# CH32V307_V2_0_0.net
KiCad netlist of a schematic drawn in EasyEDA Pro
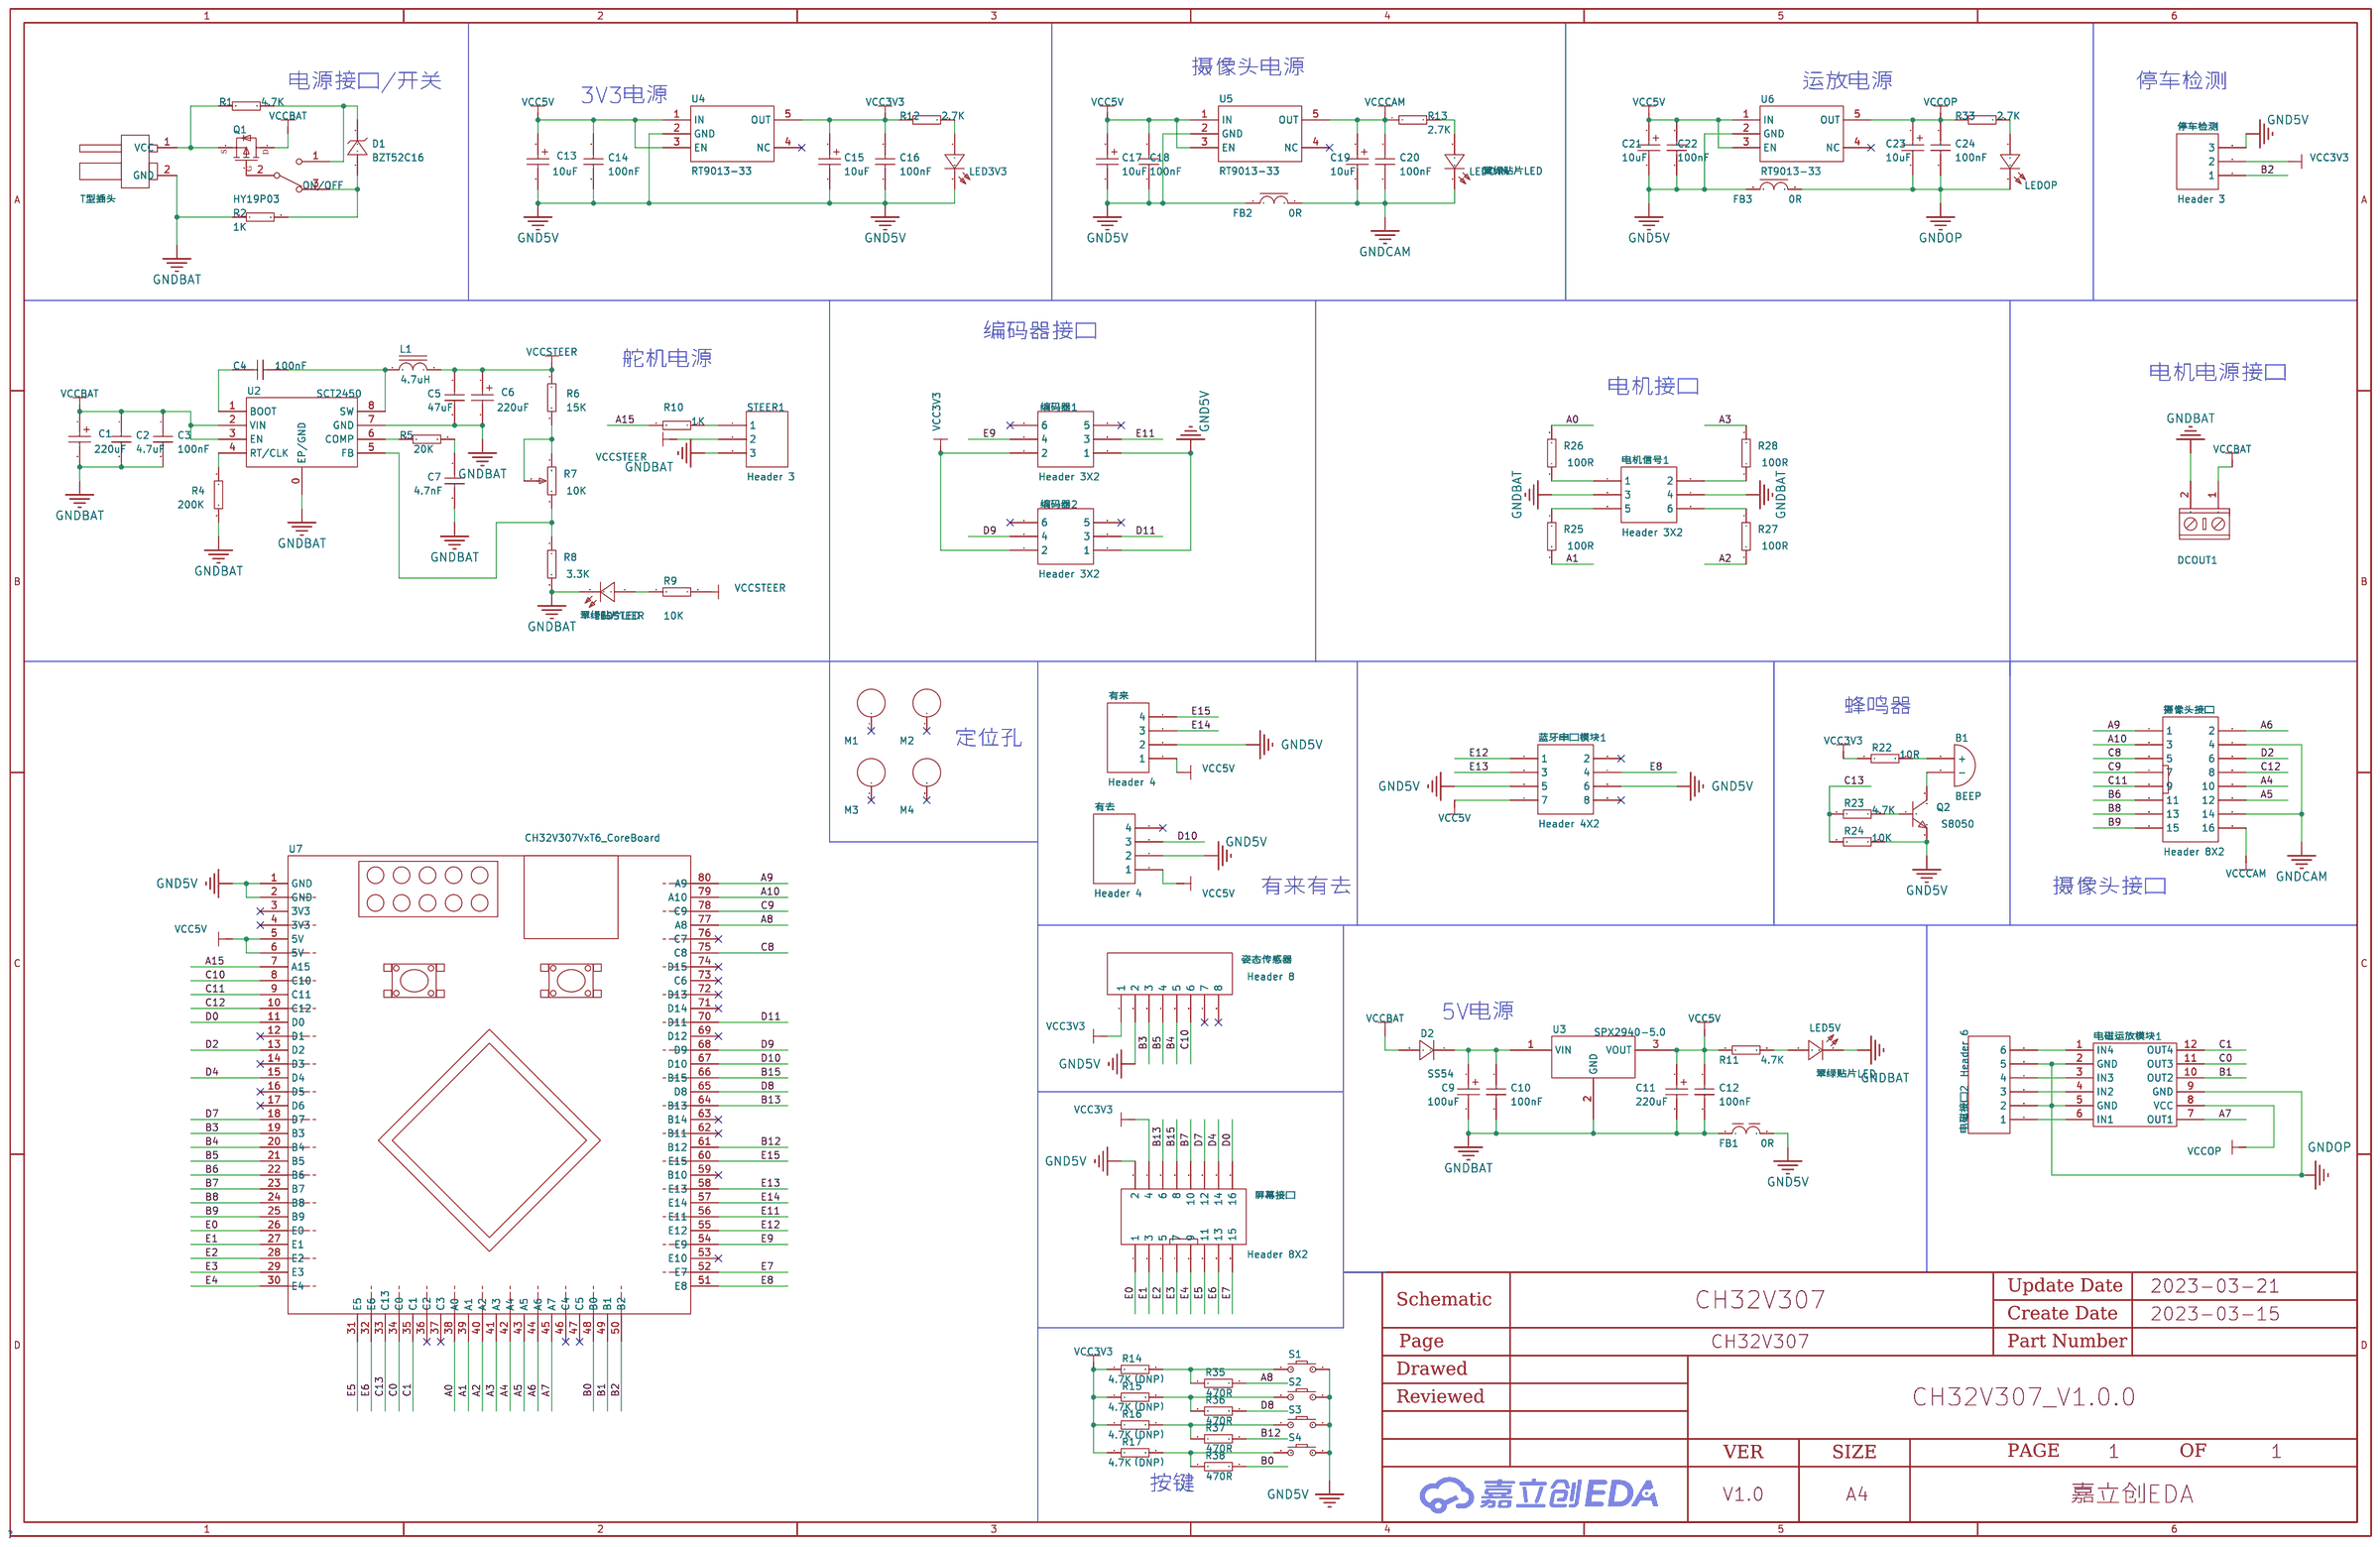
[diagram p0: schematic sheet]

(export (version "E")
  (design (tool "Eeschema 10.0.6"))
  (components
    (comp (ref "B1")
      (value "BEEP")
      (footprint "easyedapro:BEEP 9x5.5mm")
      (libsource (lib "easyedapro") (part "BEEP"))
    )
    (comp (ref "C1")
      (value "220uF")
      (footprint "easyedapro:CAPS6.3")
      (fields (field (name "Voltage") "25V") (field (name "Publisher") "Altium Limited"))
      (libsource (lib "easyedapro") (part "Cap-Solid_1"))
    )
    (comp (ref "C2")
      (value "4.7nF")
      (footprint "easyedapro:CAPC1608[0603]S-N")
      (fields (field (name "Tolerance") "±10%") (field (name "Voltage") "50V"))
      (libsource (lib "easyedapro") (part "Cap-Chip_3"))
    )
    (comp (ref "C3")
      (value "100nF")
      (footprint "easyedapro:CAPC1608[0603]S-N")
      (fields (field (name "Tolerance") "±10%") (field (name "Voltage") "50V"))
      (libsource (lib "easyedapro") (part "Cap-Chip"))
    )
    (comp (ref "C4")
      (value "100nF")
      (footprint "easyedapro:CAPC1608[0603]S-N")
      (libsource (lib "easyedapro") (part "Cap-Chip"))
    )
    (comp (ref "C5")
      (value "47uF")
      (footprint "easyedapro:CAPC3216[1206]S")
      (fields (field (name "Tolerance") "±10%") (field (name "Voltage") "16V"))
      (libsource (lib "easyedapro") (part "Cap-Chip_2"))
    )
    (comp (ref "C6")
      (value "220uF")
      (footprint "easyedapro:CAPS6.3")
      (fields (field (name "Voltage") "25V") (field (name "Publisher") "Altium Limited"))
      (libsource (lib "easyedapro") (part "Cap-Solid_1"))
    )
    (comp (ref "C7")
      (value "4.7nF")
      (footprint "easyedapro:CAPC1608[0603]S-N")
      (fields (field (name "Tolerance") "±10%") (field (name "Voltage") "50V"))
      (libsource (lib "easyedapro") (part "Cap-Chip_3"))
    )
    (comp (ref "C9")
      (value "100uF")
      (footprint "easyedapro:CAPS6.3")
      (fields (field (name "Voltage") "25V") (field (name "Publisher") "Altium Limited"))
      (libsource (lib "easyedapro") (part "Cap-Solid"))
    )
    (comp (ref "C10")
      (value "100nF")
      (footprint "easyedapro:CAPC1608[0603]S-N")
      (fields (field (name "Tolerance") "±10%") (field (name "Voltage") "50V"))
      (libsource (lib "easyedapro") (part "Cap-Chip"))
    )
    (comp (ref "C11")
      (value "220uF")
      (footprint "easyedapro:CAPS6.3")
      (fields (field (name "Voltage") "25V") (field (name "Publisher") "Altium Limited"))
      (libsource (lib "easyedapro") (part "Cap-Solid_1"))
    )
    (comp (ref "C12")
      (value "100nF")
      (footprint "easyedapro:CAPC1608[0603]S-N")
      (fields (field (name "Tolerance") "±10%") (field (name "Voltage") "50V"))
      (libsource (lib "easyedapro") (part "Cap-Chip"))
    )
    (comp (ref "C13")
      (value "10uF")
      (footprint "easyedapro:CAPT3216")
      (fields (field (name "Voltage") "16V") (field (name "Publisher") "Altium Limited"))
      (libsource (lib "easyedapro") (part "Cap-Tan"))
    )
    (comp (ref "C14")
      (value "100nF")
      (footprint "easyedapro:CAPC1608[0603]S-N")
      (fields (field (name "Tolerance") "±10%") (field (name "Voltage") "50V"))
      (libsource (lib "easyedapro") (part "Cap-Chip"))
    )
    (comp (ref "C15")
      (value "10uF")
      (footprint "easyedapro:CAPT3216")
      (fields (field (name "Voltage") "16V") (field (name "Publisher") "Altium Limited"))
      (libsource (lib "easyedapro") (part "Cap-Tan"))
    )
    (comp (ref "C16")
      (value "100nF")
      (footprint "easyedapro:CAPC1608[0603]S-N")
      (fields (field (name "Tolerance") "±10%") (field (name "Voltage") "50V"))
      (libsource (lib "easyedapro") (part "Cap-Chip"))
    )
    (comp (ref "C17")
      (value "10uF")
      (footprint "easyedapro:CAPT3216")
      (fields (field (name "Voltage") "16V") (field (name "Publisher") "Altium Limited"))
      (libsource (lib "easyedapro") (part "Cap-Tan"))
    )
    (comp (ref "C18")
      (value "100nF")
      (footprint "easyedapro:CAPC1608[0603]S-N")
      (fields (field (name "Tolerance") "±10%") (field (name "Voltage") "50V"))
      (libsource (lib "easyedapro") (part "Cap-Chip"))
    )
    (comp (ref "C19")
      (value "10uF")
      (footprint "easyedapro:CAPT3216")
      (fields (field (name "Voltage") "16V") (field (name "Publisher") "Altium Limited"))
      (libsource (lib "easyedapro") (part "Cap-Tan"))
    )
    (comp (ref "C20")
      (value "100nF")
      (footprint "easyedapro:CAPC1608[0603]S-N")
      (fields (field (name "Tolerance") "±10%") (field (name "Voltage") "50V"))
      (libsource (lib "easyedapro") (part "Cap-Chip"))
    )
    (comp (ref "C21")
      (value "10uF")
      (footprint "easyedapro:CAPT3216")
      (fields (field (name "Voltage") "16V") (field (name "Publisher") "Altium Limited"))
      (libsource (lib "easyedapro") (part "Cap-Tan"))
    )
    (comp (ref "C22")
      (value "100nF")
      (footprint "easyedapro:CAPC1608[0603]S-N")
      (fields (field (name "Tolerance") "±10%") (field (name "Voltage") "50V"))
      (libsource (lib "easyedapro") (part "Cap-Chip"))
    )
    (comp (ref "C23")
      (value "10uF")
      (footprint "easyedapro:CAPT3216")
      (fields (field (name "Voltage") "16V") (field (name "Publisher") "Altium Limited"))
      (libsource (lib "easyedapro") (part "Cap-Tan"))
    )
    (comp (ref "C24")
      (value "100nF")
      (footprint "easyedapro:CAPC1608[0603]S-N")
      (fields (field (name "Tolerance") "±10%") (field (name "Voltage") "50V"))
      (libsource (lib "easyedapro") (part "Cap-Chip"))
    )
    (comp (ref "D1")
      (value "BZT52C16")
      (footprint "easyedapro:SOD-123-L")
      (fields (field (name "Publisher") "Altium Limited"))
      (libsource (lib "easyedapro") (part "Diode TVS Uni-Dir"))
    )
    (comp (ref "D2")
      (value "SS54")
      (footprint "easyedapro:SMA[DO-214AC]")
      (libsource (lib "easyedapro") (part "Diode"))
    )
    (comp (ref "DCOUT1")
      (value "KF/WJ/DG 30x connecter")
      (footprint "easyedapro:KF/WJ/DG 301-2p-5.0mm")
      (libsource (lib "easyedapro") (part "KF/WJ/DG 30x"))
    )
    (comp (ref "FB1")
      (value "0R")
      (footprint "easyedapro:INDC2012[0805]S")
      (libsource (lib "easyedapro") (part "Ind Chip 2"))
    )
    (comp (ref "FB2")
      (value "0R")
      (footprint "easyedapro:INDC2012[0805]S")
      (libsource (lib "easyedapro") (part "Ind-Chip"))
    )
    (comp (ref "FB3")
      (value "0R")
      (footprint "easyedapro:INDC2012[0805]S")
      (libsource (lib "easyedapro") (part "Ind-Chip"))
    )
    (comp (ref "L1")
      (value "4.7uH")
      (footprint "easyedapro:0630 TPC 7*7*3")
      (libsource (lib "easyedapro") (part "Ind-Power"))
    )
    (comp (ref "LED3V3")
      (value "翠绿贴片LED")
      (footprint "easyedapro:LEDC1608(0603)")
      (fields (field (name "Publisher") "Altium Limited"))
      (libsource (lib "easyedapro") (part "LED Chip Green"))
    )
    (comp (ref "LED5V")
      (value "翠绿贴片LED")
      (footprint "easyedapro:LEDC1608(0603)")
      (libsource (lib "easyedapro") (part "LED Chip Green"))
    )
    (comp (ref "LEDCAM")
      (value "翠绿贴片LED")
      (footprint "easyedapro:LEDC1608(0603)")
      (fields (field (name "Publisher") "Altium Limited"))
      (libsource (lib "easyedapro") (part "LED Chip Green"))
    )
    (comp (ref "LEDOP")
      (value "翠绿贴片LED")
      (footprint "easyedapro:LEDC1608(0603)")
      (fields (field (name "Publisher") "Altium Limited"))
      (libsource (lib "easyedapro") (part "LED Chip Green"))
    )
    (comp (ref "LEDSTEER")
      (value "翠绿贴片LED")
      (footprint "easyedapro:LEDC1608(0603)")
      (fields (field (name "Publisher") "Altium Limited"))
      (libsource (lib "easyedapro") (part "LED Chip Green"))
    )
    (comp (ref "M1")
      (value "MountHole")
      (footprint "easyedapro:M3-MountHole-Plated")
      (libsource (lib "easyedapro") (part "MountHole"))
    )
    (comp (ref "M2")
      (value "MountHole")
      (footprint "easyedapro:M3-MountHole-Plated")
      (libsource (lib "easyedapro") (part "MountHole"))
    )
    (comp (ref "M3")
      (value "MountHole")
      (footprint "easyedapro:M3-MountHole-Plated")
      (libsource (lib "easyedapro") (part "MountHole"))
    )
    (comp (ref "M4")
      (value "MountHole")
      (footprint "easyedapro:M3-MountHole-Plated")
      (libsource (lib "easyedapro") (part "MountHole"))
    )
    (comp (ref "ON/OFF")
      (value "SW-SPDT")
      (footprint "easyedapro:SS12D10")
      (fields (field (name "Publisher") "Altium Limited"))
      (libsource (lib "easyedapro") (part "SW-SPDT"))
    )
    (comp (ref "Q1")
      (value "HY19P03")
      (footprint "easyedapro:TO-252AA")
      (libsource (lib "easyedapro") (part "HY19P03"))
    )
    (comp (ref "Q2")
      (value "S8050")
      (footprint "easyedapro:SOT-23")
      (libsource (lib "easyedapro") (part "NPN S8050"))
    )
    (comp (ref "R1")
      (value "4.7K")
      (footprint "easyedapro:RESC1608[0603]S-N")
      (libsource (lib "easyedapro") (part "Res-Chip_2"))
    )
    (comp (ref "R2")
      (value "1K")
      (footprint "easyedapro:RESC1608[0603]S-N")
      (libsource (lib "easyedapro") (part "Res-Chip_1"))
    )
    (comp (ref "R4")
      (value "200K")
      (footprint "easyedapro:RESC1608[0603]S-N")
      (fields (field (name "Tolerance") "±1%"))
      (libsource (lib "easyedapro") (part "Res-Chip_4"))
    )
    (comp (ref "R5")
      (value "20K")
      (footprint "easyedapro:RESC1608[0603]S-N")
      (libsource (lib "easyedapro") (part "Res-Chip_5"))
    )
    (comp (ref "R6")
      (value "15K")
      (footprint "easyedapro:RESC1608[0603]S-N")
      (fields (field (name "Tolerance") "±1%"))
      (libsource (lib "easyedapro") (part "Res-Chip_6"))
    )
    (comp (ref "R7")
      (value "10K")
      (footprint "easyedapro:RESPOT3296")
      (libsource (lib "easyedapro") (part "Res-Adj-3p"))
    )
    (comp (ref "R8")
      (value "3.3K")
      (footprint "easyedapro:RESC1608[0603]S-N")
      (fields (field (name "Tolerance") "±1%"))
      (libsource (lib "easyedapro") (part "Res-Chip_7"))
    )
    (comp (ref "R9")
      (value "10K")
      (footprint "easyedapro:RESC1608[0603]S-N")
      (libsource (lib "easyedapro") (part "Res-Chip"))
    )
    (comp (ref "R10")
      (value "1K")
      (footprint "easyedapro:RESC1608[0603]S-N")
      (fields (field (name "Tolerance") "±1%"))
      (libsource (lib "easyedapro") (part "Res-Chip_1"))
    )
    (comp (ref "R11")
      (value "4.7K")
      (footprint "easyedapro:RESC1608[0603]S-N")
      (libsource (lib "easyedapro") (part "Res-Chip_2"))
    )
    (comp (ref "R12")
      (value "2.7K")
      (footprint "easyedapro:RESC1608[0603]S-N")
      (libsource (lib "easyedapro") (part "Res-Chip_3"))
    )
    (comp (ref "R13")
      (value "2.7K")
      (footprint "easyedapro:RESC1608[0603]S-N")
      (libsource (lib "easyedapro") (part "Res-Chip_3"))
    )
    (comp (ref "R14")
      (value "4.7K(DNP)")
      (footprint "easyedapro:RESC1608[0603]S-N")
      (libsource (lib "easyedapro") (part "Res-Chip_9"))
    )
    (comp (ref "R15")
      (value "4.7K(DNP)")
      (footprint "easyedapro:RESC1608[0603]S-N")
      (libsource (lib "easyedapro") (part "Res-Chip_9"))
    )
    (comp (ref "R16")
      (value "4.7K(DNP)")
      (footprint "easyedapro:RESC1608[0603]S-N")
      (libsource (lib "easyedapro") (part "Res-Chip_9"))
    )
    (comp (ref "R17")
      (value "4.7K(DNP)")
      (footprint "easyedapro:RESC1608[0603]S-N")
      (libsource (lib "easyedapro") (part "Res-Chip_9"))
    )
    (comp (ref "R22")
      (value "10R")
      (footprint "easyedapro:RESC1608[0603]S-N")
      (libsource (lib "easyedapro") (part "Res-Chip_10"))
    )
    (comp (ref "R23")
      (value "4.7K")
      (footprint "easyedapro:RESC1608[0603]S-N")
      (libsource (lib "easyedapro") (part "Res-Chip_2"))
    )
    (comp (ref "R24")
      (value "10K")
      (footprint "easyedapro:RESC1608[0603]S-N")
      (libsource (lib "easyedapro") (part "Res-Chip"))
    )
    (comp (ref "R25")
      (value "100R")
      (footprint "easyedapro:RESC1608[0603]S-N")
      (libsource (lib "easyedapro") (part "Res-Chip_8"))
    )
    (comp (ref "R26")
      (value "100R")
      (footprint "easyedapro:RESC1608[0603]S-N")
      (libsource (lib "easyedapro") (part "Res-Chip_8"))
    )
    (comp (ref "R27")
      (value "100R")
      (footprint "easyedapro:RESC1608[0603]S-N")
      (fields (field (name "Tolerance") "±1%"))
      (libsource (lib "easyedapro") (part "Res-Chip_8"))
    )
    (comp (ref "R28")
      (value "100R")
      (footprint "easyedapro:RESC1608[0603]S-N")
      (libsource (lib "easyedapro") (part "Res-Chip_8"))
    )
    (comp (ref "R33")
      (value "2.7K")
      (footprint "easyedapro:RESC1608[0603]S-N")
      (libsource (lib "easyedapro") (part "Res-Chip_3"))
    )
    (comp (ref "R35")
      (value "470R")
      (footprint "easyedapro:RESC1608[0603]S-N")
      (libsource (lib "easyedapro") (part "Res-Chip_11"))
    )
    (comp (ref "R36")
      (value "470R")
      (footprint "easyedapro:RESC1608[0603]S-N")
      (libsource (lib "easyedapro") (part "Res-Chip_11"))
    )
    (comp (ref "R37")
      (value "470R")
      (footprint "easyedapro:RESC1608[0603]S-N")
      (libsource (lib "easyedapro") (part "Res-Chip_11"))
    )
    (comp (ref "R38")
      (value "470R")
      (footprint "easyedapro:RESC1608[0603]S-N")
      (libsource (lib "easyedapro") (part "Res-Chip_11"))
    )
    (comp (ref "S1")
      (value "Button")
      (footprint "easyedapro:PTS810-3*4-CurvePin")
      (libsource (lib "easyedapro") (part "KEY"))
    )
    (comp (ref "S2")
      (value "Button")
      (footprint "easyedapro:PTS810-3*4-CurvePin")
      (libsource (lib "easyedapro") (part "KEY"))
    )
    (comp (ref "S3")
      (value "Button")
      (footprint "easyedapro:PTS810-3*4-CurvePin")
      (libsource (lib "easyedapro") (part "KEY"))
    )
    (comp (ref "S4")
      (value "Button")
      (footprint "easyedapro:PTS810-3*4-CurvePin")
      (libsource (lib "easyedapro") (part "KEY"))
    )
    (comp (ref "STEER1")
      (value "Header 3")
      (footprint "easyedapro:HDR1X3")
      (fields (field (name "Publisher") "Altium Limited"))
      (libsource (lib "easyedapro") (part "Header 3"))
    )
    (comp (ref "U1")
      (value "T型插头")
      (footprint "easyedapro:Wired T-Header ThroughHole")
      (libsource (lib "easyedapro") (part "T_Header"))
    )
    (comp (ref "U2")
      (value "SCT2450")
      (footprint "easyedapro:SOP-8E")
      (libsource (lib "easyedapro") (part "SCT2450"))
    )
    (comp (ref "U3")
      (value "SPX2940-5.0")
      (footprint "easyedapro:TO-263-3")
      (libsource (lib "easyedapro") (part "LM2940-5.0"))
    )
    (comp (ref "U4")
      (value "RT9013-33")
      (footprint "easyedapro:SOT-23-5")
      (libsource (lib "easyedapro") (part "RT9013-33"))
    )
    (comp (ref "U5")
      (value "RT9013-33")
      (footprint "easyedapro:SOT-23-5")
      (libsource (lib "easyedapro") (part "RT9013-33"))
    )
    (comp (ref "U6")
      (value "RT9013-33")
      (footprint "easyedapro:SOT-23-5")
      (libsource (lib "easyedapro") (part "RT9013-33"))
    )
    (comp (ref "U7")
      (value "CH32V307VxT6_CoreBoard")
      (footprint "easyedapro:CH32V307VxT6_CoreBoard")
      (libsource (lib "easyedapro") (part "CH32V307VxT6_CoreBoardV1.3"))
    )
    (comp (ref "停车检测")
      (value "Header 3")
      (footprint "easyedapro:HDR1X3")
      (fields (field (name "Publisher") "Altium Limited"))
      (libsource (lib "easyedapro") (part "Header 3"))
    )
    (comp (ref "姿态传感器")
      (value "Header 8")
      (footprint "easyedapro:HDR1X8")
      (fields (field (name "Publisher") "Altium Limited"))
      (libsource (lib "easyedapro") (part "Header 8"))
    )
    (comp (ref "屏幕接口")
      (value "Header 8X2")
      (footprint "easyedapro:HDR2X8-M-SMT")
      (fields (field (name "Publisher") "Altium Limited"))
      (libsource (lib "easyedapro") (part "Header 8X2"))
    )
    (comp (ref "摄像头接口")
      (value "Header 8X2")
      (footprint "easyedapro:HDR2X8-M-SMT")
      (libsource (lib "easyedapro") (part "Header 8X2"))
    )
    (comp (ref "有去")
      (value "Header 4")
      (footprint "easyedapro:HDR1X4")
      (fields (field (name "Publisher") "Altium Limited"))
      (libsource (lib "easyedapro") (part "Header 4"))
    )
    (comp (ref "有来")
      (value "Header 4")
      (footprint "easyedapro:HDR1X4")
      (fields (field (name "Publisher") "Altium Limited"))
      (libsource (lib "easyedapro") (part "Header 4"))
    )
    (comp (ref "电机信号1")
      (value "Header 3X2")
      (footprint "easyedapro:HDR2X3-M-SMT")
      (libsource (lib "easyedapro") (part "Header 3X2"))
    )
    (comp (ref "电磁接口2")
      (value "Header 6")
      (footprint "easyedapro:HDR1X6")
      (libsource (lib "easyedapro") (part "Header 6"))
    )
    (comp (ref "电磁运放模块1")
      (value "OPA_MOD")
      (footprint "easyedapro:SEEKFREE_4CHANEL_OPAMOD")
      (libsource (lib "easyedapro") (part "OPA_4CHANNEL_SEEKFREE"))
    )
    (comp (ref "编码器1")
      (value "Header 3X2")
      (footprint "easyedapro:HDR2X3-M-SMT")
      (fields (field (name "Publisher") "Altium Limited"))
      (libsource (lib "easyedapro") (part "Header 3X2"))
    )
    (comp (ref "编码器2")
      (value "Header 3X2")
      (footprint "easyedapro:HDR2X3-M-SMT")
      (fields (field (name "Publisher") "Altium Limited"))
      (libsource (lib "easyedapro") (part "Header 3X2"))
    )
    (comp (ref "蓝牙串口模块1")
      (value "Header 4X2")
      (footprint "easyedapro:Female-Header-2.54-SMD-8")
      (libsource (lib "easyedapro") (part "Header 4X2"))
    )
  )
  (nets
    (net (code "1") (name "/A0") (class "Default")
      (node (ref "R26") (pin "2") (pinfunction "2_2") (pintype "input"))
      (node (ref "U7") (pin "38") (pinfunction "A0_38") (pintype "input"))
    )
    (net (code "2") (name "/A1") (class "Default")
      (node (ref "R25") (pin "2") (pinfunction "2_2") (pintype "input"))
      (node (ref "U7") (pin "39") (pinfunction "A1_39") (pintype "input"))
    )
    (net (code "3") (name "/A2") (class "Default")
      (node (ref "R27") (pin "2") (pinfunction "2_2") (pintype "input"))
      (node (ref "U7") (pin "40") (pinfunction "A2_40") (pintype "input"))
    )
    (net (code "4") (name "/A3") (class "Default")
      (node (ref "R28") (pin "2") (pinfunction "2_2") (pintype "input"))
      (node (ref "U7") (pin "41") (pinfunction "A3_41") (pintype "input"))
    )
    (net (code "5") (name "/A4") (class "Default")
      (node (ref "U7") (pin "42") (pinfunction "A4_42") (pintype "input"))
      (node (ref "摄像头接口") (pin "10") (pinfunction "10_10") (pintype "input"))
    )
    (net (code "6") (name "/A5") (class "Default")
      (node (ref "U7") (pin "43") (pinfunction "A5_43") (pintype "input"))
      (node (ref "摄像头接口") (pin "12") (pinfunction "12_12") (pintype "input"))
    )
    (net (code "7") (name "/A6") (class "Default")
      (node (ref "U7") (pin "44") (pinfunction "A6_44") (pintype "input"))
      (node (ref "摄像头接口") (pin "2") (pinfunction "2_2") (pintype "input"))
    )
    (net (code "8") (name "/A7") (class "Default")
      (node (ref "U7") (pin "45") (pinfunction "A7_45") (pintype "input"))
      (node (ref "电磁运放模块1") (pin "7") (pinfunction "OUT1_7") (pintype "input"))
    )
    (net (code "9") (name "/A8") (class "Default")
      (node (ref "R35") (pin "2") (pinfunction "2_2") (pintype "input"))
      (node (ref "U7") (pin "77") (pinfunction "A8_77") (pintype "input"))
    )
    (net (code "10") (name "/A9") (class "Default")
      (node (ref "U7") (pin "80") (pinfunction "A9_80") (pintype "input"))
      (node (ref "摄像头接口") (pin "1") (pinfunction "1_1") (pintype "input"))
    )
    (net (code "11") (name "/A10") (class "Default")
      (node (ref "U7") (pin "79") (pinfunction "A10_79") (pintype "input"))
      (node (ref "摄像头接口") (pin "3") (pinfunction "3_3") (pintype "input"))
    )
    (net (code "12") (name "/A15") (class "Default")
      (node (ref "R10") (pin "2") (pinfunction "2_2") (pintype "input"))
      (node (ref "U7") (pin "7") (pinfunction "A15_7") (pintype "input"))
    )
    (net (code "13") (name "/B0") (class "Default")
      (node (ref "R38") (pin "2") (pinfunction "2_2") (pintype "input"))
      (node (ref "U7") (pin "48") (pinfunction "B0_48") (pintype "input"))
    )
    (net (code "14") (name "/B1") (class "Default")
      (node (ref "U7") (pin "49") (pinfunction "B1_49") (pintype "input"))
      (node (ref "电磁运放模块1") (pin "10") (pinfunction "OUT2_10") (pintype "input"))
    )
    (net (code "15") (name "/B2") (class "Default")
      (node (ref "U7") (pin "50") (pinfunction "B2_50") (pintype "input"))
      (node (ref "停车检测") (pin "1") (pinfunction "1_1") (pintype "input"))
    )
    (net (code "16") (name "/B3") (class "Default")
      (node (ref "U7") (pin "19") (pinfunction "B3_19") (pintype "input"))
      (node (ref "姿态传感器") (pin "3") (pinfunction "3_3") (pintype "input"))
    )
    (net (code "17") (name "/B4") (class "Default")
      (node (ref "U7") (pin "20") (pinfunction "B4_20") (pintype "input"))
      (node (ref "姿态传感器") (pin "5") (pinfunction "5_5") (pintype "input"))
    )
    (net (code "18") (name "/B5") (class "Default")
      (node (ref "U7") (pin "21") (pinfunction "B5_21") (pintype "input"))
      (node (ref "姿态传感器") (pin "4") (pinfunction "4_4") (pintype "input"))
    )
    (net (code "19") (name "/B6") (class "Default")
      (node (ref "U7") (pin "22") (pinfunction "B6_22") (pintype "input"))
      (node (ref "摄像头接口") (pin "11") (pinfunction "11_11") (pintype "input"))
    )
    (net (code "20") (name "/B7") (class "Default")
      (node (ref "U7") (pin "23") (pinfunction "B7_23") (pintype "input"))
      (node (ref "屏幕接口") (pin "10") (pinfunction "10_10") (pintype "input"))
    )
    (net (code "21") (name "/B8") (class "Default")
      (node (ref "U7") (pin "24") (pinfunction "B8_24") (pintype "input"))
      (node (ref "摄像头接口") (pin "13") (pinfunction "13_13") (pintype "input"))
    )
    (net (code "22") (name "/B9") (class "Default")
      (node (ref "U7") (pin "25") (pinfunction "B9_25") (pintype "input"))
      (node (ref "摄像头接口") (pin "15") (pinfunction "15_15") (pintype "input"))
    )
    (net (code "23") (name "/B12") (class "Default")
      (node (ref "R37") (pin "2") (pinfunction "2_2") (pintype "input"))
      (node (ref "U7") (pin "61") (pinfunction "B12_61") (pintype "input"))
    )
    (net (code "24") (name "/B13") (class "Default")
      (node (ref "U7") (pin "64") (pinfunction "B13_64") (pintype "input"))
      (node (ref "屏幕接口") (pin "6") (pinfunction "6_6") (pintype "input"))
    )
    (net (code "25") (name "/B15") (class "Default")
      (node (ref "U7") (pin "66") (pinfunction "B15_66") (pintype "input"))
      (node (ref "屏幕接口") (pin "8") (pinfunction "8_8") (pintype "input"))
    )
    (net (code "26") (name "/C0") (class "Default")
      (node (ref "U7") (pin "34") (pinfunction "C0_34") (pintype "input"))
      (node (ref "电磁运放模块1") (pin "11") (pinfunction "OUT3_11") (pintype "input"))
    )
    (net (code "27") (name "/C1") (class "Default")
      (node (ref "U7") (pin "35") (pinfunction "C1_35") (pintype "input"))
      (node (ref "电磁运放模块1") (pin "12") (pinfunction "OUT4_12") (pintype "input"))
    )
    (net (code "28") (name "/C8") (class "Default")
      (node (ref "U7") (pin "75") (pinfunction "C8_75") (pintype "input"))
      (node (ref "摄像头接口") (pin "5") (pinfunction "5_5") (pintype "input"))
    )
    (net (code "29") (name "/C9") (class "Default")
      (node (ref "U7") (pin "78") (pinfunction "C9_78") (pintype "input"))
      (node (ref "摄像头接口") (pin "7") (pinfunction "7_7") (pintype "input"))
    )
    (net (code "30") (name "/C10") (class "Default")
      (node (ref "U7") (pin "8") (pinfunction "C10_8") (pintype "input"))
      (node (ref "姿态传感器") (pin "6") (pinfunction "6_6") (pintype "input"))
    )
    (net (code "31") (name "/C11") (class "Default")
      (node (ref "U7") (pin "9") (pinfunction "C11_9") (pintype "input"))
      (node (ref "摄像头接口") (pin "9") (pinfunction "9_9") (pintype "input"))
    )
    (net (code "32") (name "/C12") (class "Default")
      (node (ref "U7") (pin "10") (pinfunction "C12_10") (pintype "input"))
      (node (ref "摄像头接口") (pin "8") (pinfunction "8_8") (pintype "input"))
    )
    (net (code "33") (name "/C13") (class "Default")
      (node (ref "R23") (pin "1") (pinfunction "1_1") (pintype "input"))
      (node (ref "R24") (pin "1") (pinfunction "1_1") (pintype "input"))
      (node (ref "U7") (pin "33") (pinfunction "C13_33") (pintype "input"))
    )
    (net (code "34") (name "/D0") (class "Default")
      (node (ref "U7") (pin "11") (pinfunction "D0_11") (pintype "input"))
      (node (ref "屏幕接口") (pin "16") (pinfunction "16_16") (pintype "input"))
    )
    (net (code "35") (name "/D2") (class "Default")
      (node (ref "U7") (pin "13") (pinfunction "D2_13") (pintype "input"))
      (node (ref "摄像头接口") (pin "6") (pinfunction "6_6") (pintype "input"))
    )
    (net (code "36") (name "/D4") (class "Default")
      (node (ref "U7") (pin "15") (pinfunction "D4_15") (pintype "input"))
      (node (ref "屏幕接口") (pin "14") (pinfunction "14_14") (pintype "input"))
    )
    (net (code "37") (name "/D7") (class "Default")
      (node (ref "U7") (pin "18") (pinfunction "D7_18") (pintype "input"))
      (node (ref "屏幕接口") (pin "12") (pinfunction "12_12") (pintype "input"))
    )
    (net (code "38") (name "/D8") (class "Default")
      (node (ref "R36") (pin "2") (pinfunction "2_2") (pintype "input"))
      (node (ref "U7") (pin "65") (pinfunction "D8_65") (pintype "input"))
    )
    (net (code "39") (name "/D9") (class "Default")
      (node (ref "U7") (pin "68") (pinfunction "D9_68") (pintype "input"))
      (node (ref "编码器2") (pin "4") (pinfunction "4_4") (pintype "input"))
    )
    (net (code "40") (name "/D10") (class "Default")
      (node (ref "U7") (pin "67") (pinfunction "D10_67") (pintype "input"))
      (node (ref "有去") (pin "3") (pinfunction "3_3") (pintype "input"))
    )
    (net (code "41") (name "/D11") (class "Default")
      (node (ref "U7") (pin "70") (pinfunction "D11_70") (pintype "input"))
      (node (ref "编码器2") (pin "3") (pinfunction "3_3") (pintype "input"))
    )
    (net (code "42") (name "/E0") (class "Default")
      (node (ref "U7") (pin "26") (pinfunction "E0_26") (pintype "input"))
      (node (ref "屏幕接口") (pin "1") (pinfunction "1_1") (pintype "input"))
    )
    (net (code "43") (name "/E1") (class "Default")
      (node (ref "U7") (pin "27") (pinfunction "E1_27") (pintype "input"))
      (node (ref "屏幕接口") (pin "3") (pinfunction "3_3") (pintype "input"))
    )
    (net (code "44") (name "/E2") (class "Default")
      (node (ref "U7") (pin "28") (pinfunction "E2_28") (pintype "input"))
      (node (ref "屏幕接口") (pin "5") (pinfunction "5_5") (pintype "input"))
    )
    (net (code "45") (name "/E3") (class "Default")
      (node (ref "U7") (pin "29") (pinfunction "E3_29") (pintype "input"))
      (node (ref "屏幕接口") (pin "7") (pinfunction "7_7") (pintype "input"))
    )
    (net (code "46") (name "/E4") (class "Default")
      (node (ref "U7") (pin "30") (pinfunction "E4_30") (pintype "input"))
      (node (ref "屏幕接口") (pin "9") (pinfunction "9_9") (pintype "input"))
    )
    (net (code "47") (name "/E5") (class "Default")
      (node (ref "U7") (pin "31") (pinfunction "E5_31") (pintype "input"))
      (node (ref "屏幕接口") (pin "11") (pinfunction "11_11") (pintype "input"))
    )
    (net (code "48") (name "/E6") (class "Default")
      (node (ref "U7") (pin "32") (pinfunction "E6_32") (pintype "input"))
      (node (ref "屏幕接口") (pin "13") (pinfunction "13_13") (pintype "input"))
    )
    (net (code "49") (name "/E7") (class "Default")
      (node (ref "U7") (pin "52") (pinfunction "E7_52") (pintype "input"))
      (node (ref "屏幕接口") (pin "15") (pinfunction "15_15") (pintype "input"))
    )
    (net (code "50") (name "/E8") (class "Default")
      (node (ref "U7") (pin "51") (pinfunction "E8_51") (pintype "input"))
      (node (ref "蓝牙串口模块1") (pin "4") (pinfunction "4_4") (pintype "input"))
    )
    (net (code "51") (name "/E9") (class "Default")
      (node (ref "U7") (pin "54") (pinfunction "E9_54") (pintype "input"))
      (node (ref "编码器1") (pin "4") (pinfunction "4_4") (pintype "input"))
    )
    (net (code "52") (name "/E11") (class "Default")
      (node (ref "U7") (pin "56") (pinfunction "E11_56") (pintype "input"))
      (node (ref "编码器1") (pin "3") (pinfunction "3_3") (pintype "input"))
    )
    (net (code "53") (name "/E12") (class "Default")
      (node (ref "U7") (pin "55") (pinfunction "E12_55") (pintype "input"))
      (node (ref "蓝牙串口模块1") (pin "1") (pinfunction "1_1") (pintype "input"))
    )
    (net (code "54") (name "/E13") (class "Default")
      (node (ref "U7") (pin "58") (pinfunction "E13_58") (pintype "input"))
      (node (ref "蓝牙串口模块1") (pin "3") (pinfunction "3_3") (pintype "input"))
    )
    (net (code "55") (name "/E14") (class "Default")
      (node (ref "U7") (pin "57") (pinfunction "E14_57") (pintype "input"))
      (node (ref "有来") (pin "3") (pinfunction "3_3") (pintype "input"))
    )
    (net (code "56") (name "/E15") (class "Default")
      (node (ref "U7") (pin "60") (pinfunction "E15_60") (pintype "input"))
      (node (ref "有来") (pin "4") (pinfunction "4_4") (pintype "input"))
    )
    (net (code "57") (name "GND5V") (class "Default")
      (node (ref "C13") (pin "2") (pinfunction "2_2") (pintype "input"))
      (node (ref "C14") (pin "2") (pinfunction "2_2") (pintype "input"))
      (node (ref "C15") (pin "2") (pinfunction "2_2") (pintype "input"))
      (node (ref "C16") (pin "2") (pinfunction "2_2") (pintype "input"))
      (node (ref "C17") (pin "2") (pinfunction "2_2") (pintype "input"))
      (node (ref "C18") (pin "2") (pinfunction "2_2") (pintype "input"))
      (node (ref "C21") (pin "2") (pinfunction "2_2") (pintype "input"))
      (node (ref "C22") (pin "2") (pinfunction "2_2") (pintype "input"))
      (node (ref "FB1") (pin "2") (pinfunction "2_2") (pintype "input"))
      (node (ref "FB2") (pin "1") (pinfunction "1_1") (pintype "input"))
      (node (ref "FB3") (pin "1") (pinfunction "1_1") (pintype "input"))
      (node (ref "LED3V3") (pin "C") (pinfunction "C_C") (pintype "input"))
      (node (ref "Q2") (pin "2") (pinfunction "E_2") (pintype "input"))
      (node (ref "R24") (pin "2") (pinfunction "2_2") (pintype "input"))
      (node (ref "S1") (pin "1") (pinfunction "1_1") (pintype "input"))
      (node (ref "S2") (pin "1") (pinfunction "1_1") (pintype "input"))
      (node (ref "S3") (pin "1") (pinfunction "1_1") (pintype "input"))
      (node (ref "S4") (pin "1") (pinfunction "1_1") (pintype "input"))
      (node (ref "U4") (pin "2") (pinfunction "GND_2") (pintype "input"))
      (node (ref "U5") (pin "2") (pinfunction "GND_2") (pintype "input"))
      (node (ref "U6") (pin "2") (pinfunction "GND_2") (pintype "input"))
      (node (ref "U7") (pin "1") (pinfunction "GND_1") (pintype "input"))
      (node (ref "U7") (pin "2") (pinfunction "GND_2") (pintype "input"))
      (node (ref "停车检测") (pin "3") (pinfunction "3_3") (pintype "input"))
      (node (ref "姿态传感器") (pin "2") (pinfunction "2_2") (pintype "input"))
      (node (ref "屏幕接口") (pin "2") (pinfunction "2_2") (pintype "input"))
      (node (ref "有去") (pin "2") (pinfunction "2_2") (pintype "input"))
      (node (ref "有来") (pin "2") (pinfunction "2_2") (pintype "input"))
      (node (ref "编码器1") (pin "1") (pinfunction "1_1") (pintype "input"))
      (node (ref "编码器2") (pin "1") (pinfunction "1_1") (pintype "input"))
      (node (ref "蓝牙串口模块1") (pin "5") (pinfunction "5_5") (pintype "input"))
      (node (ref "蓝牙串口模块1") (pin "6") (pinfunction "6_6") (pintype "input"))
    )
    (net (code "58") (name "GNDBAT") (class "Default")
      (node (ref "C1") (pin "2") (pinfunction "2_2") (pintype "input"))
      (node (ref "C10") (pin "2") (pinfunction "2_2") (pintype "input"))
      (node (ref "C11") (pin "2") (pinfunction "2_2") (pintype "input"))
      (node (ref "C12") (pin "2") (pinfunction "2_2") (pintype "input"))
      (node (ref "C2") (pin "2") (pinfunction "2_2") (pintype "input"))
      (node (ref "C3") (pin "2") (pinfunction "2_2") (pintype "input"))
      (node (ref "C5") (pin "2") (pinfunction "2_2") (pintype "input"))
      (node (ref "C6") (pin "2") (pinfunction "2_2") (pintype "input"))
      (node (ref "C7") (pin "2") (pinfunction "2_2") (pintype "input"))
      (node (ref "C9") (pin "2") (pinfunction "2_2") (pintype "input"))
      (node (ref "DCOUT1") (pin "2") (pinfunction "2_2") (pintype "input"))
      (node (ref "FB1") (pin "1") (pinfunction "1_1") (pintype "input"))
      (node (ref "LED5V") (pin "C") (pinfunction "C_C") (pintype "input"))
      (node (ref "LEDSTEER") (pin "C") (pinfunction "C_C") (pintype "input"))
      (node (ref "R2") (pin "1") (pinfunction "1_1") (pintype "input"))
      (node (ref "R4") (pin "2") (pinfunction "2_2") (pintype "input"))
      (node (ref "R8") (pin "2") (pinfunction "2_2") (pintype "input"))
      (node (ref "STEER1") (pin "3") (pinfunction "3_3") (pintype "input"))
      (node (ref "U1") (pin "2") (pinfunction "GND_2") (pintype "input"))
      (node (ref "U2") (pin "0") (pinfunction "EP/GND_0") (pintype "input"))
      (node (ref "U2") (pin "7") (pinfunction "GND_7") (pintype "input"))
      (node (ref "U3") (pin "2") (pinfunction "GND_2") (pintype "input"))
      (node (ref "电机信号1") (pin "3") (pinfunction "3_3") (pintype "input"))
      (node (ref "电机信号1") (pin "4") (pinfunction "4_4") (pintype "input"))
    )
    (net (code "59") (name "GNDCAM") (class "Default")
      (node (ref "C19") (pin "2") (pinfunction "2_2") (pintype "input"))
      (node (ref "C20") (pin "2") (pinfunction "2_2") (pintype "input"))
      (node (ref "FB2") (pin "2") (pinfunction "2_2") (pintype "input"))
      (node (ref "LEDCAM") (pin "C") (pinfunction "C_C") (pintype "input"))
      (node (ref "摄像头接口") (pin "14") (pinfunction "14_14") (pintype "input"))
      (node (ref "摄像头接口") (pin "4") (pinfunction "4_4") (pintype "input"))
    )
    (net (code "60") (name "GNDOP") (class "Default")
      (node (ref "C23") (pin "2") (pinfunction "2_2") (pintype "input"))
      (node (ref "C24") (pin "2") (pinfunction "2_2") (pintype "input"))
      (node (ref "FB3") (pin "2") (pinfunction "2_2") (pintype "input"))
      (node (ref "LEDOP") (pin "C") (pinfunction "C_C") (pintype "input"))
      (node (ref "电磁接口2") (pin "2") (pinfunction "2_2") (pintype "input"))
      (node (ref "电磁接口2") (pin "5") (pinfunction "5_5") (pintype "input"))
      (node (ref "电磁运放模块1") (pin "2") (pinfunction "GND_2") (pintype "input"))
      (node (ref "电磁运放模块1") (pin "5") (pinfunction "GND_5") (pintype "input"))
      (node (ref "电磁运放模块1") (pin "9") (pinfunction "GND_9") (pintype "input"))
    )
    (net (code "61") (name "Net-(B1-+)") (class "Default")
      (node (ref "B1") (pin "1") (pinfunction "+_1") (pintype "input"))
      (node (ref "R22") (pin "2") (pinfunction "2_2") (pintype "input"))
    )
    (net (code "62") (name "Net-(B1--)") (class "Default")
      (node (ref "B1") (pin "2") (pinfunction "-_2") (pintype "input"))
      (node (ref "Q2") (pin "3") (pinfunction "C_3") (pintype "input"))
    )
    (net (code "63") (name "Net-(C7-Pad1)") (class "Default")
      (node (ref "C7") (pin "1") (pinfunction "1_1") (pintype "input"))
      (node (ref "R5") (pin "2") (pinfunction "2_2") (pintype "input"))
    )
    (net (code "64") (name "Net-(D1-PadA)") (class "Default")
      (node (ref "D1") (pin "A") (pinfunction "A_A") (pintype "input"))
      (node (ref "ON/OFF") (pin "3") (pintype "input"))
      (node (ref "R2") (pin "2") (pinfunction "2_2") (pintype "input"))
    )
    (net (code "65") (name "Net-(D1-PadK)") (class "Default")
      (node (ref "D1") (pin "K") (pinfunction "K_K") (pintype "input"))
      (node (ref "ON/OFF") (pin "1") (pintype "input"))
      (node (ref "R1") (pin "2") (pinfunction "2_2") (pintype "input"))
    )
    (net (code "66") (name "Net-(LED3V3-PadA)") (class "Default")
      (node (ref "LED3V3") (pin "A") (pinfunction "A_A") (pintype "input"))
      (node (ref "R12") (pin "2") (pinfunction "2_2") (pintype "input"))
    )
    (net (code "67") (name "Net-(LED5V-PadA)") (class "Default")
      (node (ref "LED5V") (pin "A") (pinfunction "A_A") (pintype "input"))
      (node (ref "R11") (pin "2") (pinfunction "2_2") (pintype "input"))
    )
    (net (code "68") (name "Net-(LEDCAM-PadA)") (class "Default")
      (node (ref "LEDCAM") (pin "A") (pinfunction "A_A") (pintype "input"))
      (node (ref "R13") (pin "2") (pinfunction "2_2") (pintype "input"))
    )
    (net (code "69") (name "Net-(LEDOP-PadA)") (class "Default")
      (node (ref "LEDOP") (pin "A") (pinfunction "A_A") (pintype "input"))
      (node (ref "R33") (pin "2") (pinfunction "2_2") (pintype "input"))
    )
    (net (code "70") (name "Net-(LEDSTEER-PadA)") (class "Default")
      (node (ref "LEDSTEER") (pin "A") (pinfunction "A_A") (pintype "input"))
      (node (ref "R9") (pin "1") (pinfunction "1_1") (pintype "input"))
    )
    (net (code "71") (name "Net-(Q1-G)") (class "Default")
      (node (ref "ON/OFF") (pin "2") (pintype "input"))
      (node (ref "Q1") (pin "2") (pinfunction "G_2") (pintype "input"))
    )
    (net (code "72") (name "Net-(Q1-S)") (class "Default")
      (node (ref "Q1") (pin "3") (pinfunction "S_3") (pintype "input"))
      (node (ref "R1") (pin "1") (pinfunction "1_1") (pintype "input"))
      (node (ref "U1") (pin "1") (pinfunction "VCC_1") (pintype "input"))
    )
    (net (code "73") (name "Net-(Q2-B)") (class "Default")
      (node (ref "Q2") (pin "1") (pinfunction "B_1") (pintype "input"))
      (node (ref "R23") (pin "2") (pinfunction "2_2") (pintype "input"))
    )
    (net (code "74") (name "Net-(R7-BOT)") (class "Default")
      (node (ref "R7") (pin "2") (pinfunction "BOT_2") (pintype "input"))
      (node (ref "R8") (pin "1") (pinfunction "1_1") (pintype "input"))
      (node (ref "U2") (pin "5") (pinfunction "FB_5") (pintype "input"))
    )
    (net (code "75") (name "Net-(R7-TOP)") (class "Default")
      (node (ref "R6") (pin "2") (pinfunction "2_2") (pintype "input"))
      (node (ref "R7") (pin "1") (pinfunction "TOP_1") (pintype "input"))
      (node (ref "R7") (pin "ADJ") (pinfunction "ADJ_ADJ") (pintype "input"))
    )
    (net (code "76") (name "Net-(R10-Pad1)") (class "Default")
      (node (ref "R10") (pin "1") (pinfunction "1_1") (pintype "input"))
      (node (ref "STEER1") (pin "1") (pinfunction "1_1") (pintype "input"))
    )
    (net (code "77") (name "Net-(R14-Pad2)") (class "Default")
      (node (ref "R14") (pin "2") (pinfunction "2_2") (pintype "input"))
      (node (ref "R35") (pin "1") (pinfunction "1_1") (pintype "input"))
      (node (ref "S1") (pin "2") (pinfunction "2_2") (pintype "input"))
    )
    (net (code "78") (name "Net-(R15-Pad2)") (class "Default")
      (node (ref "R15") (pin "2") (pinfunction "2_2") (pintype "input"))
      (node (ref "R36") (pin "1") (pinfunction "1_1") (pintype "input"))
      (node (ref "S2") (pin "2") (pinfunction "2_2") (pintype "input"))
    )
    (net (code "79") (name "Net-(R16-Pad2)") (class "Default")
      (node (ref "R16") (pin "2") (pinfunction "2_2") (pintype "input"))
      (node (ref "R37") (pin "1") (pinfunction "1_1") (pintype "input"))
      (node (ref "S3") (pin "2") (pinfunction "2_2") (pintype "input"))
    )
    (net (code "80") (name "Net-(R17-Pad2)") (class "Default")
      (node (ref "R17") (pin "2") (pinfunction "2_2") (pintype "input"))
      (node (ref "R38") (pin "1") (pinfunction "1_1") (pintype "input"))
      (node (ref "S4") (pin "2") (pinfunction "2_2") (pintype "input"))
    )
    (net (code "81") (name "Net-(R25-Pad1)") (class "Default")
      (node (ref "R25") (pin "1") (pinfunction "1_1") (pintype "input"))
      (node (ref "电机信号1") (pin "5") (pinfunction "5_5") (pintype "input"))
    )
    (net (code "82") (name "Net-(R26-Pad1)") (class "Default")
      (node (ref "R26") (pin "1") (pinfunction "1_1") (pintype "input"))
      (node (ref "电机信号1") (pin "1") (pinfunction "1_1") (pintype "input"))
    )
    (net (code "83") (name "Net-(R27-Pad1)") (class "Default")
      (node (ref "R27") (pin "1") (pinfunction "1_1") (pintype "input"))
      (node (ref "电机信号1") (pin "6") (pinfunction "6_6") (pintype "input"))
    )
    (net (code "84") (name "Net-(R28-Pad1)") (class "Default")
      (node (ref "R28") (pin "1") (pinfunction "1_1") (pintype "input"))
      (node (ref "电机信号1") (pin "2") (pinfunction "2_2") (pintype "input"))
    )
    (net (code "85") (name "Net-(U2-BOOT)") (class "Default")
      (node (ref "C4") (pin "1") (pinfunction "1_1") (pintype "input"))
      (node (ref "U2") (pin "1") (pinfunction "BOOT_1") (pintype "input"))
    )
    (net (code "86") (name "Net-(U2-COMP)") (class "Default")
      (node (ref "R5") (pin "1") (pinfunction "1_1") (pintype "input"))
      (node (ref "U2") (pin "6") (pinfunction "COMP_6") (pintype "input"))
    )
    (net (code "87") (name "Net-(U2-RT{slash}CLK)") (class "Default")
      (node (ref "R4") (pin "1") (pinfunction "1_1") (pintype "input"))
      (node (ref "U2") (pin "4") (pinfunction "RT/CLK_4") (pintype "input"))
    )
    (net (code "88") (name "Net-(U2-SW)") (class "Default")
      (node (ref "C4") (pin "2") (pinfunction "2_2") (pintype "input"))
      (node (ref "L1") (pin "1") (pinfunction "1_1") (pintype "input"))
      (node (ref "U2") (pin "8") (pinfunction "SW_8") (pintype "input"))
    )
    (net (code "89") (name "Net-(U3-VIN)") (class "Default")
      (node (ref "C10") (pin "1") (pinfunction "1_1") (pintype "input"))
      (node (ref "C9") (pin "1") (pinfunction "1_1") (pintype "input"))
      (node (ref "D2") (pin "K") (pinfunction "K_K") (pintype "input"))
      (node (ref "U3") (pin "1") (pinfunction "VIN_1") (pintype "input"))
    )
    (net (code "90") (name "Net-(电磁运放模块1-IN1)") (class "Default")
      (node (ref "电磁接口2") (pin "1") (pinfunction "1_1") (pintype "input"))
      (node (ref "电磁运放模块1") (pin "6") (pinfunction "IN1_6") (pintype "input"))
    )
    (net (code "91") (name "Net-(电磁运放模块1-IN2)") (class "Default")
      (node (ref "电磁接口2") (pin "3") (pinfunction "3_3") (pintype "input"))
      (node (ref "电磁运放模块1") (pin "4") (pinfunction "IN2_4") (pintype "input"))
    )
    (net (code "92") (name "Net-(电磁运放模块1-IN3)") (class "Default")
      (node (ref "电磁接口2") (pin "4") (pinfunction "4_4") (pintype "input"))
      (node (ref "电磁运放模块1") (pin "3") (pinfunction "IN3_3") (pintype "input"))
    )
    (net (code "93") (name "Net-(电磁运放模块1-IN4)") (class "Default")
      (node (ref "电磁接口2") (pin "6") (pinfunction "6_6") (pintype "input"))
      (node (ref "电磁运放模块1") (pin "1") (pinfunction "IN4_1") (pintype "input"))
    )
    (net (code "94") (name "VCC3V3") (class "Default")
      (node (ref "C15") (pin "1") (pinfunction "1_1") (pintype "input"))
      (node (ref "C16") (pin "1") (pinfunction "1_1") (pintype "input"))
      (node (ref "R12") (pin "1") (pinfunction "1_1") (pintype "input"))
      (node (ref "R14") (pin "1") (pinfunction "1_1") (pintype "input"))
      (node (ref "R15") (pin "1") (pinfunction "1_1") (pintype "input"))
      (node (ref "R16") (pin "1") (pinfunction "1_1") (pintype "input"))
      (node (ref "R17") (pin "1") (pinfunction "1_1") (pintype "input"))
      (node (ref "R22") (pin "1") (pinfunction "1_1") (pintype "input"))
      (node (ref "U4") (pin "5") (pinfunction "OUT_5") (pintype "input"))
      (node (ref "停车检测") (pin "2") (pinfunction "2_2") (pintype "input"))
      (node (ref "姿态传感器") (pin "1") (pinfunction "1_1") (pintype "input"))
      (node (ref "屏幕接口") (pin "4") (pinfunction "4_4") (pintype "input"))
      (node (ref "编码器1") (pin "2") (pinfunction "2_2") (pintype "input"))
      (node (ref "编码器2") (pin "2") (pinfunction "2_2") (pintype "input"))
    )
    (net (code "95") (name "VCC5V") (class "Default")
      (node (ref "C11") (pin "1") (pinfunction "1_1") (pintype "input"))
      (node (ref "C12") (pin "1") (pinfunction "1_1") (pintype "input"))
      (node (ref "C13") (pin "1") (pinfunction "1_1") (pintype "input"))
      (node (ref "C14") (pin "1") (pinfunction "1_1") (pintype "input"))
      (node (ref "C17") (pin "1") (pinfunction "1_1") (pintype "input"))
      (node (ref "C18") (pin "1") (pinfunction "1_1") (pintype "input"))
      (node (ref "C21") (pin "1") (pinfunction "1_1") (pintype "input"))
      (node (ref "C22") (pin "1") (pinfunction "1_1") (pintype "input"))
      (node (ref "R11") (pin "1") (pinfunction "1_1") (pintype "input"))
      (node (ref "U3") (pin "3") (pinfunction "VOUT_3") (pintype "input"))
      (node (ref "U4") (pin "1") (pinfunction "IN_1") (pintype "input"))
      (node (ref "U4") (pin "3") (pinfunction "EN_3") (pintype "input"))
      (node (ref "U5") (pin "1") (pinfunction "IN_1") (pintype "input"))
      (node (ref "U5") (pin "3") (pinfunction "EN_3") (pintype "input"))
      (node (ref "U6") (pin "1") (pinfunction "IN_1") (pintype "input"))
      (node (ref "U6") (pin "3") (pinfunction "EN_3") (pintype "input"))
      (node (ref "U7") (pin "5") (pinfunction "5V_5") (pintype "input"))
      (node (ref "U7") (pin "6") (pinfunction "5V_6") (pintype "input"))
      (node (ref "有去") (pin "1") (pinfunction "1_1") (pintype "input"))
      (node (ref "有来") (pin "1") (pinfunction "1_1") (pintype "input"))
      (node (ref "蓝牙串口模块1") (pin "7") (pinfunction "7_7") (pintype "input"))
    )
    (net (code "96") (name "VCCBAT") (class "Default")
      (node (ref "C1") (pin "1") (pinfunction "1_1") (pintype "input"))
      (node (ref "C2") (pin "1") (pinfunction "1_1") (pintype "input"))
      (node (ref "C3") (pin "1") (pinfunction "1_1") (pintype "input"))
      (node (ref "D2") (pin "A") (pinfunction "A_A") (pintype "input"))
      (node (ref "DCOUT1") (pin "1") (pinfunction "1_1") (pintype "input"))
      (node (ref "Q1") (pin "1") (pinfunction "D_1") (pintype "input"))
      (node (ref "U2") (pin "2") (pinfunction "VIN_2") (pintype "input"))
      (node (ref "U2") (pin "3") (pinfunction "EN_3") (pintype "input"))
    )
    (net (code "97") (name "VCCCAM") (class "Default")
      (node (ref "C19") (pin "1") (pinfunction "1_1") (pintype "input"))
      (node (ref "C20") (pin "1") (pinfunction "1_1") (pintype "input"))
      (node (ref "R13") (pin "1") (pinfunction "1_1") (pintype "input"))
      (node (ref "U5") (pin "5") (pinfunction "OUT_5") (pintype "input"))
      (node (ref "摄像头接口") (pin "16") (pinfunction "16_16") (pintype "input"))
    )
    (net (code "98") (name "VCCOP") (class "Default")
      (node (ref "C23") (pin "1") (pinfunction "1_1") (pintype "input"))
      (node (ref "C24") (pin "1") (pinfunction "1_1") (pintype "input"))
      (node (ref "R33") (pin "1") (pinfunction "1_1") (pintype "input"))
      (node (ref "U6") (pin "5") (pinfunction "OUT_5") (pintype "input"))
      (node (ref "电磁运放模块1") (pin "8") (pinfunction "VCC_8") (pintype "input"))
    )
    (net (code "99") (name "VCCSTEER") (class "Default")
      (node (ref "C5") (pin "1") (pinfunction "1_1") (pintype "input"))
      (node (ref "C6") (pin "1") (pinfunction "1_1") (pintype "input"))
      (node (ref "L1") (pin "2") (pinfunction "2_2") (pintype "input"))
      (node (ref "R6") (pin "1") (pinfunction "1_1") (pintype "input"))
      (node (ref "R9") (pin "2") (pinfunction "2_2") (pintype "input"))
      (node (ref "STEER1") (pin "2") (pinfunction "2_2") (pintype "input"))
    )
    (net (code "100") (name "unconnected-(M1-Pad1)") (class "Default")
      (node (ref "M1") (pin "1") (pinfunction "1_1") (pintype "input+no_connect"))
    )
    (net (code "101") (name "unconnected-(M2-Pad1)") (class "Default")
      (node (ref "M2") (pin "1") (pinfunction "1_1") (pintype "input+no_connect"))
    )
    (net (code "102") (name "unconnected-(M3-Pad1)") (class "Default")
      (node (ref "M3") (pin "1") (pinfunction "1_1") (pintype "input+no_connect"))
    )
    (net (code "103") (name "unconnected-(M4-Pad1)") (class "Default")
      (node (ref "M4") (pin "1") (pinfunction "1_1") (pintype "input+no_connect"))
    )
    (net (code "104") (name "unconnected-(U4-NC-Pad4)") (class "Default")
      (node (ref "U4") (pin "4") (pinfunction "NC_4") (pintype "input+no_connect"))
    )
    (net (code "105") (name "unconnected-(U5-NC-Pad4)") (class "Default")
      (node (ref "U5") (pin "4") (pinfunction "NC_4") (pintype "input+no_connect"))
    )
    (net (code "106") (name "unconnected-(U6-NC-Pad4)") (class "Default")
      (node (ref "U6") (pin "4") (pinfunction "NC_4") (pintype "input+no_connect"))
    )
    (net (code "107") (name "unconnected-(U7-3V3-Pad3)") (class "Default")
      (node (ref "U7") (pin "3") (pinfunction "3V3_3") (pintype "input+no_connect"))
    )
    (net (code "108") (name "unconnected-(U7-3V3-Pad4)") (class "Default")
      (node (ref "U7") (pin "4") (pinfunction "3V3_4") (pintype "input+no_connect"))
    )
    (net (code "109") (name "unconnected-(U7-B10-Pad59)") (class "Default")
      (node (ref "U7") (pin "59") (pinfunction "B10_59") (pintype "input+no_connect"))
    )
    (net (code "110") (name "unconnected-(U7-B11-Pad62)") (class "Default")
      (node (ref "U7") (pin "62") (pinfunction "B11_62") (pintype "input+no_connect"))
    )
    (net (code "111") (name "unconnected-(U7-B14-Pad63)") (class "Default")
      (node (ref "U7") (pin "63") (pinfunction "B14_63") (pintype "input+no_connect"))
    )
    (net (code "112") (name "unconnected-(U7-C2-Pad36)") (class "Default")
      (node (ref "U7") (pin "36") (pinfunction "C2_36") (pintype "input+no_connect"))
    )
    (net (code "113") (name "unconnected-(U7-C3-Pad37)") (class "Default")
      (node (ref "U7") (pin "37") (pinfunction "C3_37") (pintype "input+no_connect"))
    )
    (net (code "114") (name "unconnected-(U7-C4-Pad46)") (class "Default")
      (node (ref "U7") (pin "46") (pinfunction "C4_46") (pintype "input+no_connect"))
    )
    (net (code "115") (name "unconnected-(U7-C5-Pad47)") (class "Default")
      (node (ref "U7") (pin "47") (pinfunction "C5_47") (pintype "input+no_connect"))
    )
    (net (code "116") (name "unconnected-(U7-C6-Pad73)") (class "Default")
      (node (ref "U7") (pin "73") (pinfunction "C6_73") (pintype "input+no_connect"))
    )
    (net (code "117") (name "unconnected-(U7-C7-Pad76)") (class "Default")
      (node (ref "U7") (pin "76") (pinfunction "C7_76") (pintype "input+no_connect"))
    )
    (net (code "118") (name "unconnected-(U7-D1-Pad12)") (class "Default")
      (node (ref "U7") (pin "12") (pinfunction "D1_12") (pintype "input+no_connect"))
    )
    (net (code "119") (name "unconnected-(U7-D3-Pad14)") (class "Default")
      (node (ref "U7") (pin "14") (pinfunction "D3_14") (pintype "input+no_connect"))
    )
    (net (code "120") (name "unconnected-(U7-D5-Pad16)") (class "Default")
      (node (ref "U7") (pin "16") (pinfunction "D5_16") (pintype "input+no_connect"))
    )
    (net (code "121") (name "unconnected-(U7-D6-Pad17)") (class "Default")
      (node (ref "U7") (pin "17") (pinfunction "D6_17") (pintype "input+no_connect"))
    )
    (net (code "122") (name "unconnected-(U7-D12-Pad69)") (class "Default")
      (node (ref "U7") (pin "69") (pinfunction "D12_69") (pintype "input+no_connect"))
    )
    (net (code "123") (name "unconnected-(U7-D13-Pad72)") (class "Default")
      (node (ref "U7") (pin "72") (pinfunction "D13_72") (pintype "input+no_connect"))
    )
    (net (code "124") (name "unconnected-(U7-D14-Pad71)") (class "Default")
      (node (ref "U7") (pin "71") (pinfunction "D14_71") (pintype "input+no_connect"))
    )
    (net (code "125") (name "unconnected-(U7-D15-Pad74)") (class "Default")
      (node (ref "U7") (pin "74") (pinfunction "D15_74") (pintype "input+no_connect"))
    )
    (net (code "126") (name "unconnected-(U7-E10-Pad53)") (class "Default")
      (node (ref "U7") (pin "53") (pinfunction "E10_53") (pintype "input+no_connect"))
    )
    (net (code "127") (name "unconnected-(姿态传感器-Pad7)") (class "Default")
      (node (ref "姿态传感器") (pin "7") (pinfunction "7_7") (pintype "input+no_connect"))
    )
    (net (code "128") (name "unconnected-(姿态传感器-Pad8)") (class "Default")
      (node (ref "姿态传感器") (pin "8") (pinfunction "8_8") (pintype "input+no_connect"))
    )
    (net (code "129") (name "unconnected-(有去-Pad4)") (class "Default")
      (node (ref "有去") (pin "4") (pinfunction "4_4") (pintype "input+no_connect"))
    )
    (net (code "130") (name "unconnected-(编码器1-Pad5)") (class "Default")
      (node (ref "编码器1") (pin "5") (pinfunction "5_5") (pintype "input+no_connect"))
    )
    (net (code "131") (name "unconnected-(编码器1-Pad6)") (class "Default")
      (node (ref "编码器1") (pin "6") (pinfunction "6_6") (pintype "input+no_connect"))
    )
    (net (code "132") (name "unconnected-(编码器2-Pad5)") (class "Default")
      (node (ref "编码器2") (pin "5") (pinfunction "5_5") (pintype "input+no_connect"))
    )
    (net (code "133") (name "unconnected-(编码器2-Pad6)") (class "Default")
      (node (ref "编码器2") (pin "6") (pinfunction "6_6") (pintype "input+no_connect"))
    )
    (net (code "134") (name "unconnected-(蓝牙串口模块1-Pad2)") (class "Default")
      (node (ref "蓝牙串口模块1") (pin "2") (pinfunction "2_2") (pintype "input+no_connect"))
    )
    (net (code "135") (name "unconnected-(蓝牙串口模块1-Pad8)") (class "Default")
      (node (ref "蓝牙串口模块1") (pin "8") (pinfunction "8_8") (pintype "input+no_connect"))
    )
  )
)
